# USER_IO.net
KiCad netlist of a schematic drawn in Altium Designer
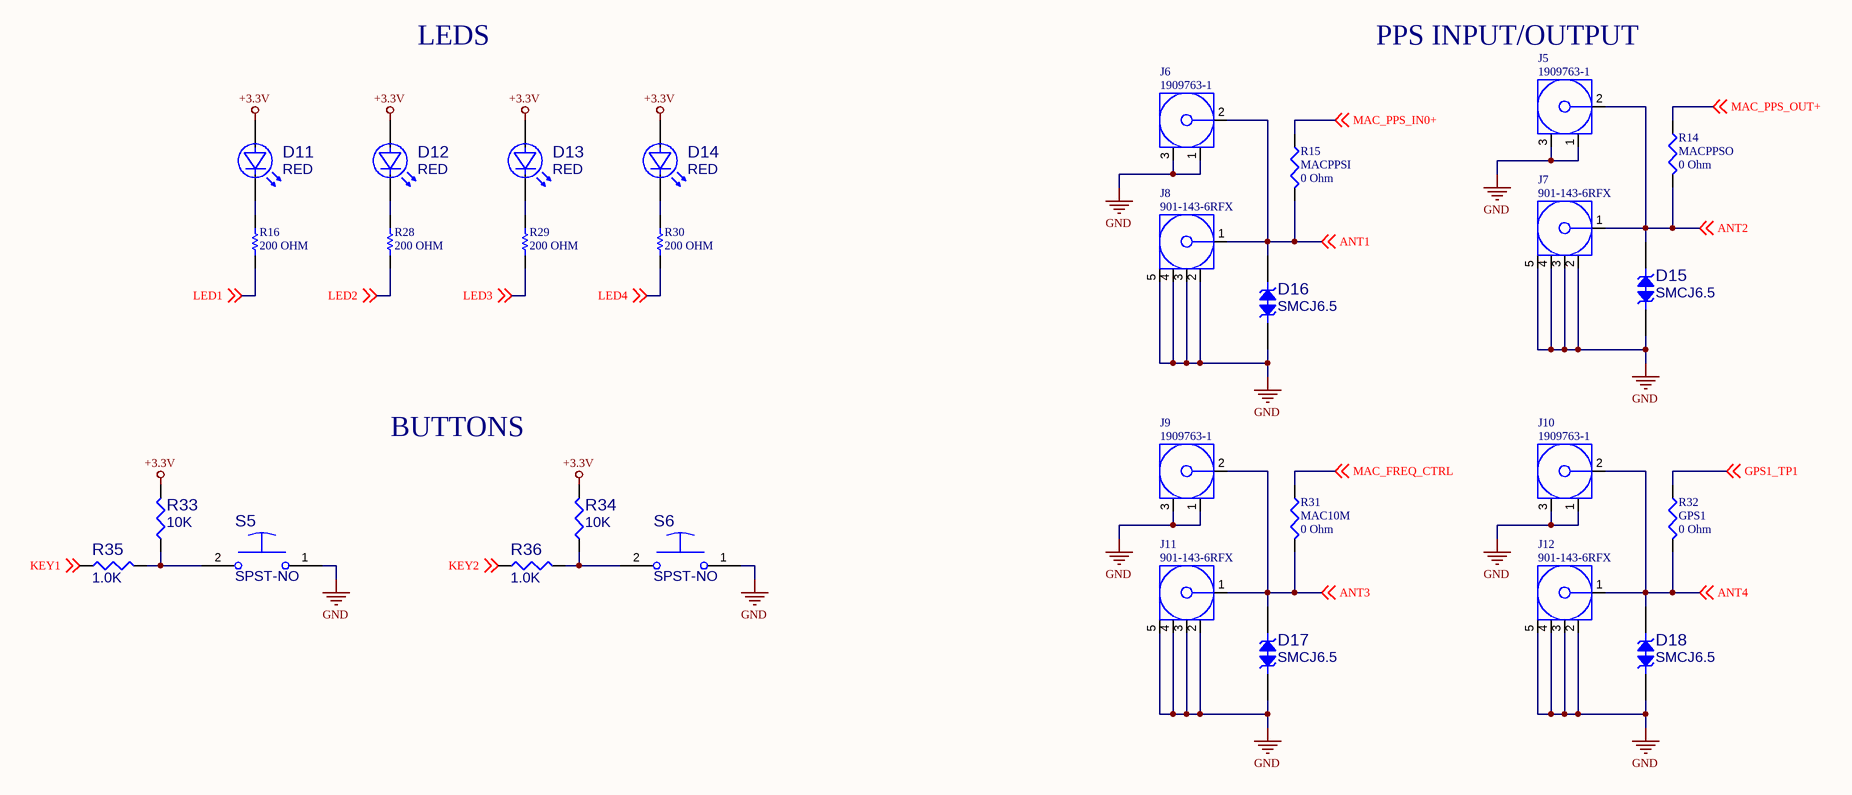
[diagram p0: USER_IO.SchDoc]

(export (version "E")
  (design (tool "Eeschema 10.0.6"))
  (components
    (comp (ref "D11")
      (value "RED")
      (footprint "DIOM1608X06N")
      (description "LED, RED, SML-LX0603, 635NM, 2V, 20MA, 0603")
      (fields
        (field (name "MFG PART NUM") "SML-LX0603IW-TR")
        (field (name "VALENTIUM PART NUM") "<VALENTIUM>")
      )
      (libsource (lib "Passives") (part "SMTLED_RED_0603_SML"))
    )
    (comp (ref "D12")
      (value "RED")
      (footprint "DIOM1608X06N")
      (description "LED, RED, SML-LX0603, 635NM, 2V, 20MA, 0603")
      (fields
        (field (name "MFG PART NUM") "SML-LX0603IW-TR")
        (field (name "VALENTIUM PART NUM") "<VALENTIUM>")
      )
      (libsource (lib "Passives") (part "SMTLED_RED_0603_SML"))
    )
    (comp (ref "D13")
      (value "RED")
      (footprint "DIOM1608X06N")
      (description "LED, RED, SML-LX0603, 635NM, 2V, 20MA, 0603")
      (fields
        (field (name "MFG PART NUM") "SML-LX0603IW-TR")
        (field (name "VALENTIUM PART NUM") "<VALENTIUM>")
      )
      (libsource (lib "Passives") (part "SMTLED_RED_0603_SML"))
    )
    (comp (ref "D14")
      (value "RED")
      (footprint "DIOM1608X06N")
      (description "LED, RED, SML-LX0603, 635NM, 2V, 20MA, 0603")
      (fields
        (field (name "MFG PART NUM") "SML-LX0603IW-TR")
        (field (name "VALENTIUM PART NUM") "<VALENTIUM>")
      )
      (libsource (lib "Passives") (part "SMTLED_RED_0603_SML"))
    )
    (comp (ref "D15")
      (value "SMCJ6.5")
      (footprint "DIOM6959X26N")
      (description "DIO, TVS, SMCJ6.5, 6.5V, BIDIR, 1.5KW, SMC")
      (fields (field (name "MFG PART NUM") "SMCJ6.5CA") (field (name "VALENTIUM PART NUM") "<VALENTIUM>"))
      (libsource (lib "Passives") (part "SMCJ6.5CA"))
    )
    (comp (ref "D16")
      (value "SMCJ6.5")
      (footprint "DIOM6959X26N")
      (description "DIO, TVS, SMCJ6.5, 6.5V, BIDIR, 1.5KW, SMC")
      (fields (field (name "MFG PART NUM") "SMCJ6.5CA") (field (name "VALENTIUM PART NUM") "<VALENTIUM>"))
      (libsource (lib "Passives") (part "SMCJ6.5CA"))
    )
    (comp (ref "D17")
      (value "SMCJ6.5")
      (footprint "DIOM6959X26N")
      (description "DIO, TVS, SMCJ6.5, 6.5V, BIDIR, 1.5KW, SMC")
      (fields (field (name "MFG PART NUM") "SMCJ6.5CA") (field (name "VALENTIUM PART NUM") "<VALENTIUM>"))
      (libsource (lib "Passives") (part "SMCJ6.5CA"))
    )
    (comp (ref "D18")
      (value "SMCJ6.5")
      (footprint "DIOM6959X26N")
      (description "DIO, TVS, SMCJ6.5, 6.5V, BIDIR, 1.5KW, SMC")
      (fields (field (name "MFG PART NUM") "SMCJ6.5CA") (field (name "VALENTIUM PART NUM") "<VALENTIUM>"))
      (libsource (lib "Passives") (part "SMCJ6.5CA"))
    )
    (comp (ref "J5")
      (value "1909763-1")
      (footprint "TECO-1909763-1_V")
      (description "Ultra Miniature Coaxial Connector Jack, 60 V, 50 Ohm, -40 to 90 degC, RoHS, Tape and Reel")
      (fields (field (name "MANUFACTURER") "TE Connectivity"))
      (libsource (lib "Altium Content Vault") (part "CN-1P-M-RF3"))
    )
    (comp (ref "J6")
      (value "1909763-1")
      (footprint "TECO-1909763-1_V")
      (description "Ultra Miniature Coaxial Connector Jack, 60 V, 50 Ohm, -40 to 90 degC, RoHS, Tape and Reel")
      (fields (field (name "MANUFACTURER") "TE Connectivity"))
      (libsource (lib "Altium Content Vault") (part "CN-1P-M-RF3"))
    )
    (comp (ref "J7")
      (value "901-143-6RFX")
      (footprint "AMPH-901-143-6RFX_V")
      (description "Coaxial connector, 50 Ohm, -65 to 165 degC, 5-Pin THD, RoHS, Bulk")
      (fields (field (name "MANUFACTURER") "Amphenol"))
      (libsource (lib "Altium Content Vault") (part "CN-S-4F-RF5"))
    )
    (comp (ref "J8")
      (value "901-143-6RFX")
      (footprint "AMPH-901-143-6RFX_V")
      (description "Coaxial connector, 50 Ohm, -65 to 165 degC, 5-Pin THD, RoHS, Bulk")
      (fields (field (name "MANUFACTURER") "Amphenol"))
      (libsource (lib "Altium Content Vault") (part "CN-S-4F-RF5"))
    )
    (comp (ref "J9")
      (value "1909763-1")
      (footprint "TECO-1909763-1_V")
      (description "Ultra Miniature Coaxial Connector Jack, 60 V, 50 Ohm, -40 to 90 degC, RoHS, Tape and Reel")
      (fields (field (name "MANUFACTURER") "TE Connectivity"))
      (libsource (lib "Altium Content Vault") (part "CN-1P-M-RF3"))
    )
    (comp (ref "J10")
      (value "1909763-1")
      (footprint "TECO-1909763-1_V")
      (description "Ultra Miniature Coaxial Connector Jack, 60 V, 50 Ohm, -40 to 90 degC, RoHS, Tape and Reel")
      (fields (field (name "MANUFACTURER") "TE Connectivity"))
      (libsource (lib "Altium Content Vault") (part "CN-1P-M-RF3"))
    )
    (comp (ref "J11")
      (value "901-143-6RFX")
      (footprint "AMPH-901-143-6RFX_V")
      (description "Coaxial connector, 50 Ohm, -65 to 165 degC, 5-Pin THD, RoHS, Bulk")
      (fields (field (name "MANUFACTURER") "Amphenol"))
      (libsource (lib "Altium Content Vault") (part "CN-S-4F-RF5"))
    )
    (comp (ref "J12")
      (value "901-143-6RFX")
      (footprint "AMPH-901-143-6RFX_V")
      (description "Coaxial connector, 50 Ohm, -65 to 165 degC, 5-Pin THD, RoHS, Bulk")
      (fields (field (name "MANUFACTURER") "Amphenol"))
      (libsource (lib "Altium Content Vault") (part "CN-S-4F-RF5"))
    )
    (comp (ref "R14")
      (value "MACPPSO")
      (footprint "J1-0603")
      (description "Resistor")
      (fields (field (name "ALTIUM_VALUE") "0 Ohm") (field (name "PUBLISHER") "Altium Limited"))
      (libsource (lib "Miscellaneous Devices") (part "Res3"))
    )
    (comp (ref "R15")
      (value "MACPPSI")
      (footprint "J1-0603")
      (description "Resistor")
      (fields (field (name "ALTIUM_VALUE") "0 Ohm") (field (name "PUBLISHER") "Altium Limited"))
      (libsource (lib "Miscellaneous Devices") (part "Res3"))
    )
    (comp (ref "R16")
      (value "200 OHM")
      (footprint "RESC1608X55X30NL15T15")
      (description "ERJ-3EKF2000V")
      (fields (field (name "MANUFACTURER") "Panasonic"))
      (libsource (lib "Altium Content Vault") (part "RES"))
    )
    (comp (ref "R28")
      (value "200 OHM")
      (footprint "RESC1608X55X30NL15T15")
      (description "ERJ-3EKF2000V")
      (fields (field (name "MANUFACTURER") "Panasonic"))
      (libsource (lib "Altium Content Vault") (part "RES"))
    )
    (comp (ref "R29")
      (value "200 OHM")
      (footprint "RESC1608X55X30NL15T15")
      (description "ERJ-3EKF2000V")
      (fields (field (name "MANUFACTURER") "Panasonic"))
      (libsource (lib "Altium Content Vault") (part "RES"))
    )
    (comp (ref "R30")
      (value "200 OHM")
      (footprint "RESC1608X55X30NL15T15")
      (description "ERJ-3EKF2000V")
      (fields (field (name "MANUFACTURER") "Panasonic"))
      (libsource (lib "Altium Content Vault") (part "RES"))
    )
    (comp (ref "R31")
      (value "MAC10M")
      (footprint "J1-0603")
      (description "Resistor")
      (fields (field (name "ALTIUM_VALUE") "0 Ohm") (field (name "PUBLISHER") "Altium Limited"))
      (libsource (lib "Miscellaneous Devices") (part "Res3"))
    )
    (comp (ref "R32")
      (value "GPS1")
      (footprint "J1-0603")
      (description "Resistor")
      (fields (field (name "ALTIUM_VALUE") "0 Ohm") (field (name "PUBLISHER") "Altium Limited"))
      (libsource (lib "Miscellaneous Devices") (part "Res3"))
    )
    (comp (ref "R33")
      (value "10K")
      (footprint "RESC1608X50N")
      (description "RES, 10K, 1%, 1/10W, TF, 0603")
      (fields (field (name "MFG PART NUM") "ERJ-3EKF1002V") (field (name "VELENTIUM PART NUM") "<VELENTIUM>"))
      (libsource (lib "Resistors") (part "RES_0603_10K"))
    )
    (comp (ref "R34")
      (value "10K")
      (footprint "RESC1608X50N")
      (description "RES, 10K, 1%, 1/10W, TF, 0603")
      (fields (field (name "MFG PART NUM") "ERJ-3EKF1002V") (field (name "VELENTIUM PART NUM") "<VELENTIUM>"))
      (libsource (lib "Resistors") (part "RES_0603_10K"))
    )
    (comp (ref "R35")
      (value "1.0K")
      (footprint "RESC1608X50N")
      (description "RES, 1.0K, 1%, 1/10W, TF, 0603")
      (fields (field (name "MFG PART NUM") "ERJ-3EKF1001V") (field (name "VELENTIUM PART NUM") "<VELENTIUM>"))
      (libsource (lib "Resistors") (part "RES_0603_1.0K"))
    )
    (comp (ref "R36")
      (value "1.0K")
      (footprint "RESC1608X50N")
      (description "RES, 1.0K, 1%, 1/10W, TF, 0603")
      (fields (field (name "MFG PART NUM") "ERJ-3EKF1001V") (field (name "VELENTIUM PART NUM") "<VELENTIUM>"))
      (libsource (lib "Resistors") (part "RES_0603_1.0K"))
    )
    (comp (ref "S5")
      (value "SPST-NO")
      (footprint "OMRON-B3U-1000P")
      (description "SW, SPST-NO, TACT, 12V, 50MA, 3X2.5MM SMT, B3U SERIES")
      (fields (field (name "MFG PART NUM") "B3U-1000P") (field (name "VALENTIUM PART NUM") "<VALENTIUM>"))
      (libsource (lib "Miscellaneous") (part "B3U-1000P"))
    )
    (comp (ref "S6")
      (value "SPST-NO")
      (footprint "OMRON-B3U-1000P")
      (description "SW, SPST-NO, TACT, 12V, 50MA, 3X2.5MM SMT, B3U SERIES")
      (fields (field (name "MFG PART NUM") "B3U-1000P") (field (name "VALENTIUM PART NUM") "<VALENTIUM>"))
      (libsource (lib "Miscellaneous") (part "B3U-1000P"))
    )
  )
  (nets
    (net (code "1") (name "+3.3V") (class "Default")
      (node (ref "D11") (pin "2") (pinfunction "A_2") (pintype "passive"))
      (node (ref "D12") (pin "2") (pinfunction "A_2") (pintype "passive"))
      (node (ref "D13") (pin "2") (pinfunction "A_2") (pintype "passive"))
      (node (ref "D14") (pin "2") (pinfunction "A_2") (pintype "passive"))
      (node (ref "R33") (pin "2") (pinfunction "2_2") (pintype "passive"))
      (node (ref "R34") (pin "2") (pinfunction "2_2") (pintype "passive"))
    )
    (net (code "2") (name "ANT1") (class "Default")
      (node (ref "D16") (pin "A") (pinfunction "A_A") (pintype "passive"))
      (node (ref "J6") (pin "2") (pinfunction "2_2") (pintype "passive"))
      (node (ref "J8") (pin "1") (pinfunction "1_1") (pintype "passive"))
      (node (ref "R15") (pin "2") (pinfunction "2_2") (pintype "passive"))
    )
    (net (code "3") (name "ANT2") (class "Default")
      (node (ref "D15") (pin "A") (pinfunction "A_A") (pintype "passive"))
      (node (ref "J5") (pin "2") (pinfunction "2_2") (pintype "passive"))
      (node (ref "J7") (pin "1") (pinfunction "1_1") (pintype "passive"))
      (node (ref "R14") (pin "2") (pinfunction "2_2") (pintype "passive"))
    )
    (net (code "4") (name "ANT3") (class "Default")
      (node (ref "D17") (pin "A") (pinfunction "A_A") (pintype "passive"))
      (node (ref "J11") (pin "1") (pinfunction "1_1") (pintype "passive"))
      (node (ref "J9") (pin "2") (pinfunction "2_2") (pintype "passive"))
      (node (ref "R31") (pin "2") (pinfunction "2_2") (pintype "passive"))
    )
    (net (code "5") (name "ANT4") (class "Default")
      (node (ref "D18") (pin "A") (pinfunction "A_A") (pintype "passive"))
      (node (ref "J10") (pin "2") (pinfunction "2_2") (pintype "passive"))
      (node (ref "J12") (pin "1") (pinfunction "1_1") (pintype "passive"))
      (node (ref "R32") (pin "2") (pinfunction "2_2") (pintype "passive"))
    )
    (net (code "6") (name "GND") (class "Default")
      (node (ref "D15") (pin "K") (pinfunction "K_K") (pintype "passive"))
      (node (ref "D16") (pin "K") (pinfunction "K_K") (pintype "passive"))
      (node (ref "D17") (pin "K") (pinfunction "K_K") (pintype "passive"))
      (node (ref "D18") (pin "K") (pinfunction "K_K") (pintype "passive"))
      (node (ref "J10") (pin "1") (pinfunction "1_1") (pintype "passive"))
      (node (ref "J10") (pin "3") (pinfunction "3_3") (pintype "passive"))
      (node (ref "J11") (pin "2") (pinfunction "2_2") (pintype "passive"))
      (node (ref "J11") (pin "3") (pinfunction "3_3") (pintype "passive"))
      (node (ref "J11") (pin "4") (pinfunction "4_4") (pintype "passive"))
      (node (ref "J11") (pin "5") (pinfunction "5_5") (pintype "passive"))
      (node (ref "J12") (pin "2") (pinfunction "2_2") (pintype "passive"))
      (node (ref "J12") (pin "3") (pinfunction "3_3") (pintype "passive"))
      (node (ref "J12") (pin "4") (pinfunction "4_4") (pintype "passive"))
      (node (ref "J12") (pin "5") (pinfunction "5_5") (pintype "passive"))
      (node (ref "J5") (pin "1") (pinfunction "1_1") (pintype "passive"))
      (node (ref "J5") (pin "3") (pinfunction "3_3") (pintype "passive"))
      (node (ref "J6") (pin "1") (pinfunction "1_1") (pintype "passive"))
      (node (ref "J6") (pin "3") (pinfunction "3_3") (pintype "passive"))
      (node (ref "J7") (pin "2") (pinfunction "2_2") (pintype "passive"))
      (node (ref "J7") (pin "3") (pinfunction "3_3") (pintype "passive"))
      (node (ref "J7") (pin "4") (pinfunction "4_4") (pintype "passive"))
      (node (ref "J7") (pin "5") (pinfunction "5_5") (pintype "passive"))
      (node (ref "J8") (pin "2") (pinfunction "2_2") (pintype "passive"))
      (node (ref "J8") (pin "3") (pinfunction "3_3") (pintype "passive"))
      (node (ref "J8") (pin "4") (pinfunction "4_4") (pintype "passive"))
      (node (ref "J8") (pin "5") (pinfunction "5_5") (pintype "passive"))
      (node (ref "J9") (pin "1") (pinfunction "1_1") (pintype "passive"))
      (node (ref "J9") (pin "3") (pinfunction "3_3") (pintype "passive"))
      (node (ref "S5") (pin "1") (pintype "passive"))
      (node (ref "S6") (pin "1") (pintype "passive"))
    )
    (net (code "7") (name "GPS1_TP1") (class "Default")
      (node (ref "R32") (pin "1") (pinfunction "1_1") (pintype "passive"))
    )
    (net (code "8") (name "KEY1") (class "Default")
      (node (ref "R35") (pin "1") (pinfunction "1_1") (pintype "passive"))
    )
    (net (code "9") (name "KEY2") (class "Default")
      (node (ref "R36") (pin "1") (pinfunction "1_1") (pintype "passive"))
    )
    (net (code "10") (name "LED1") (class "Default")
      (node (ref "R16") (pin "1") (pinfunction "1_1") (pintype "passive"))
    )
    (net (code "11") (name "LED2") (class "Default")
      (node (ref "R28") (pin "1") (pinfunction "1_1") (pintype "passive"))
    )
    (net (code "12") (name "LED3") (class "Default")
      (node (ref "R29") (pin "1") (pinfunction "1_1") (pintype "passive"))
    )
    (net (code "13") (name "LED4") (class "Default")
      (node (ref "R30") (pin "1") (pinfunction "1_1") (pintype "passive"))
    )
    (net (code "14") (name "MAC_FREQ_CTRL") (class "Default")
      (node (ref "R31") (pin "1") (pinfunction "1_1") (pintype "passive"))
    )
    (net (code "15") (name "MAC_PPS_IN0+") (class "Default")
      (node (ref "R15") (pin "1") (pinfunction "1_1") (pintype "passive"))
    )
    (net (code "16") (name "MAC_PPS_OUT+") (class "Default")
      (node (ref "R14") (pin "1") (pinfunction "1_1") (pintype "passive"))
    )
    (net (code "17") (name "Net-(D11-K)") (class "Default")
      (node (ref "D11") (pin "1") (pinfunction "K_1") (pintype "passive"))
      (node (ref "R16") (pin "2") (pinfunction "2_2") (pintype "passive"))
    )
    (net (code "18") (name "Net-(D12-K)") (class "Default")
      (node (ref "D12") (pin "1") (pinfunction "K_1") (pintype "passive"))
      (node (ref "R28") (pin "2") (pinfunction "2_2") (pintype "passive"))
    )
    (net (code "19") (name "Net-(D13-K)") (class "Default")
      (node (ref "D13") (pin "1") (pinfunction "K_1") (pintype "passive"))
      (node (ref "R29") (pin "2") (pinfunction "2_2") (pintype "passive"))
    )
    (net (code "20") (name "Net-(D14-K)") (class "Default")
      (node (ref "D14") (pin "1") (pinfunction "K_1") (pintype "passive"))
      (node (ref "R30") (pin "2") (pinfunction "2_2") (pintype "passive"))
    )
    (net (code "21") (name "Net-(R33-Pad1)") (class "Default")
      (node (ref "R33") (pin "1") (pinfunction "1_1") (pintype "passive"))
      (node (ref "R35") (pin "2") (pinfunction "2_2") (pintype "passive"))
      (node (ref "S5") (pin "2") (pintype "passive"))
    )
    (net (code "22") (name "Net-(R34-Pad1)") (class "Default")
      (node (ref "R34") (pin "1") (pinfunction "1_1") (pintype "passive"))
      (node (ref "R36") (pin "2") (pinfunction "2_2") (pintype "passive"))
      (node (ref "S6") (pin "2") (pintype "passive"))
    )
  )
)
